# Tweeter_Right.net
KiCad netlist of a schematic drawn in Altium Designer
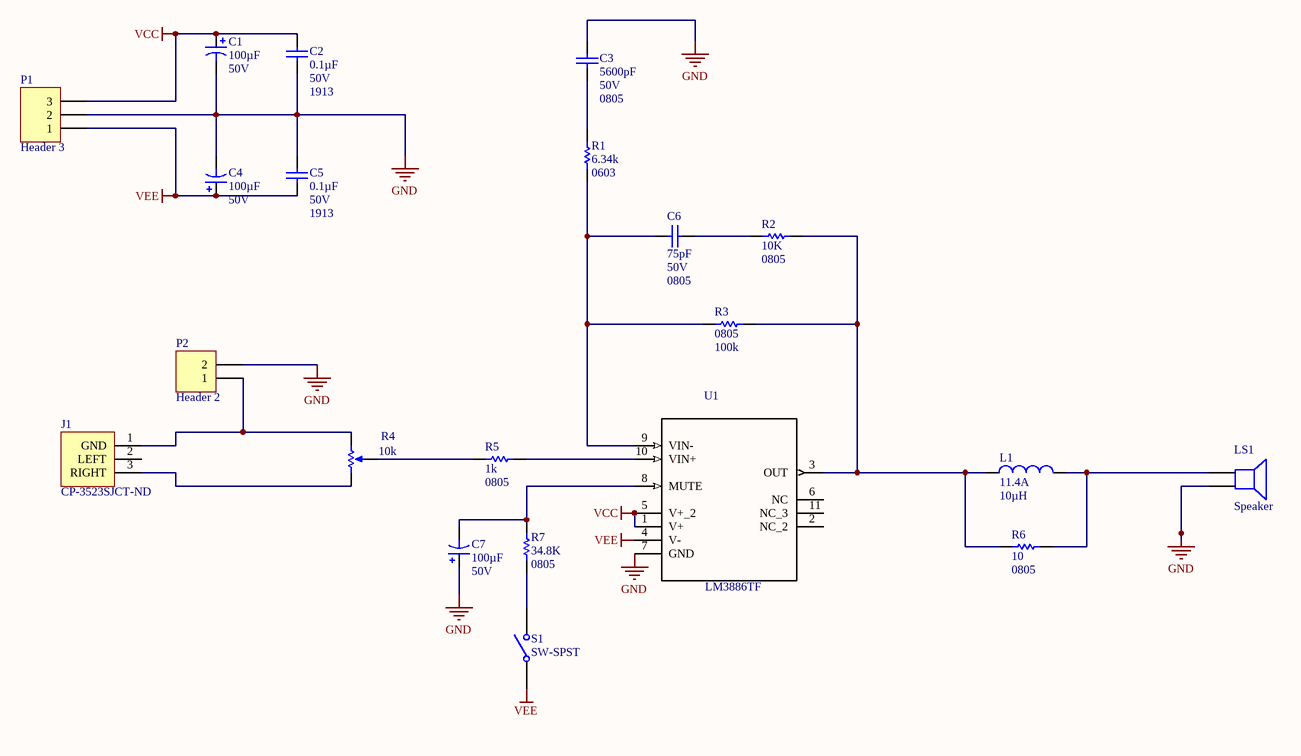
[diagram p0: Tweeter Right.SchDoc]

(export (version "E")
  (design (tool "Eeschema 10.0.6"))
  (components
    (comp (ref "C1")
      (value "UUQ1H101MCL1GS")
      (footprint "CAPAE109103X103M")
      (description "CAP ALUM 100UF 20% 50V SMD")
      (fields
        (field (name "TOLERANCE") "±20%")
        (field (name "CAPACITANCE") "100µF")
        (field (name "VOLTAGE - RATED") "50V")
      )
      (libsource (lib "Capacitors") (part "UUQ1H101MCL1GS"))
    )
    (comp (ref "C2")
      (value "ECH-U1H104JX9")
      (footprint "CAP1913")
      (description "CAP FILM 0.1UF 5% 50VDC 1913")
      (fields
        (field (name "TOLERANCE") "±5%")
        (field (name "CAPACITANCE") "0.1µF")
        (field (name "VOLTAGE RATING - DC") "50V")
        (field (name "PACKAGE / CASE") "1913")
      )
      (libsource (lib "Capacitors") (part "ECH-U1H104JX9"))
    )
    (comp (ref "C3")
      (value "C2012C0G1H562J060AA")
      (footprint "CAP0805")
      (description "CAP CER 5600PF 50V C0G 0805")
      (fields
        (field (name "CAPACITANCE") "5600pF")
        (field (name "VOLTAGE - RATED") "50V")
        (field (name "PACKAGE") "0805")
      )
      (libsource (lib "Capacitors") (part "C2012C0G1H562J060AA"))
    )
    (comp (ref "C4")
      (value "UUQ1H101MCL1GS")
      (footprint "CAPAE109103X103M")
      (description "CAP ALUM 100UF 20% 50V SMD")
      (fields
        (field (name "TOLERANCE") "±20%")
        (field (name "CAPACITANCE") "100µF")
        (field (name "VOLTAGE - RATED") "50V")
      )
      (libsource (lib "Capacitors") (part "UUQ1H101MCL1GS"))
    )
    (comp (ref "C5")
      (value "ECH-U1H104JX9")
      (footprint "CAP1913")
      (description "CAP FILM 0.1UF 5% 50VDC 1913")
      (fields
        (field (name "TOLERANCE") "±5%")
        (field (name "CAPACITANCE") "0.1µF")
        (field (name "VOLTAGE RATING - DC") "50V")
        (field (name "PACKAGE / CASE") "1913")
      )
      (libsource (lib "Capacitors") (part "ECH-U1H104JX9"))
    )
    (comp (ref "C6")
      (value "C0805C750J5GAC7800")
      (footprint "CAP0805")
      (description "CAP CER 75PF 50V NP0 0805")
      (fields
        (field (name "CAPACITANCE") "75pF")
        (field (name "VOLTAGE - RATED") "50V")
        (field (name "PACKAGE") "0805")
      )
      (libsource (lib "Capacitors") (part "C0805C750J5GAC7800"))
    )
    (comp (ref "C7")
      (value "UUQ1H101MCL1GS")
      (footprint "CAPAE109103X103M")
      (description "CAP ALUM 100UF 20% 50V SMD")
      (fields
        (field (name "TOLERANCE") "±20%")
        (field (name "CAPACITANCE") "100µF")
        (field (name "VOLTAGE - RATED") "50V")
      )
      (libsource (lib "Capacitors") (part "UUQ1H101MCL1GS"))
    )
    (comp (ref "J1")
      (value "SJ-3523-SMT-TR")
      (footprint "CONN JACK STEREO 3.5MM SMD R/A")
      (description "CONN JACK STEREO 3.5MM SMD R/A")
      (fields (field (name "SUPPLIER PART NUMBER 1") "CP-3523SJCT-ND"))
      (libsource (lib "Mechanical_Devices") (part "SJ-3523-SMT-TR"))
    )
    (comp (ref "L1")
      (value "2100LL-100-V-RC")
      (footprint "Shielded Toroidal Inductor")
      (description "FIXED IND 10UH 11.4A 5 MOHM TH")
      (fields
        (field (name "TOLERANCE") "±15%")
        (field (name "CURRENT RATING") "11.4A")
        (field (name "INDUCTANCE") "10µH")
      )
      (libsource (lib "Inductors") (part "2100LL-100-V-RC"))
    )
    (comp (ref "LS1")
      (value "Speaker")
      (footprint "PIN2")
      (description "Loudspeaker")
      (fields (field (name "PUBLISHER") "Altium Limited"))
      (libsource (lib "Miscellaneous Devices") (part "Speaker"))
    )
    (comp (ref "P1")
      (value "Header 3")
      (footprint "HDR1X3")
      (description "Header, 3-Pin")
      (fields (field (name "PUBLISHER") "Altium Limited"))
      (libsource (lib "Miscellaneous Connectors") (part "Header 3"))
    )
    (comp (ref "P2")
      (value "Header 2")
      (footprint "HDR1X2")
      (description "Header, 2-Pin")
      (fields (field (name "PUBLISHER") "Altium Limited"))
      (libsource (lib "Miscellaneous Connectors") (part "Header 2"))
    )
    (comp (ref "R1")
      (value "RT0603DRD076K34L")
      (footprint "RES0603")
      (description "RES SMD 6.34KOHM 0.5% 1/10W 0603")
      (fields (field (name "RESISTANCE") "6.34k") (field (name "PACKAGE") "0603"))
      (libsource (lib "Resistors") (part "RT0603DRD076K34L"))
    )
    (comp (ref "R2")
      (value "RT0805BRE0710KL")
      (footprint "RES0805")
      (description "RES SMD 10K OHM 0.1% 1/8W 0805")
      (fields (field (name "RESISTANCE") "10K") (field (name "PACKAGE") "0805"))
      (libsource (lib "Resistors") (part "RT0805BRE0710KL"))
    )
    (comp (ref "R3")
      (value "ERA-6AEB104V")
      (footprint "RES0805")
      (description "RES SMD 100K OHM 0.1% 1/8W 0805")
      (fields (field (name "PACKAGE") "0805") (field (name "RESISTANCE") "100k"))
      (libsource (lib "Resistors") (part "ERA-6AEB104V"))
    )
    (comp (ref "R4")
      (value "10k")
      (footprint "VR5")
      (description "Potentiometer")
      (fields (field (name "Comment") "RPot") (field (name "PUBLISHER") "Altium Limited"))
      (libsource (lib "Miscellaneous Devices") (part "RPot"))
    )
    (comp (ref "R5")
      (value "RT0805FRE071KL")
      (footprint "RES0805")
      (description "RES SMD 1K OHM 1% 1/8W 0805")
      (fields (field (name "RESISTANCE") "1k") (field (name "PACKAGE") "0805"))
      (libsource (lib "Resistors") (part "RT0805FRE071KL"))
    )
    (comp (ref "R6")
      (value "RNCP0805FTD10R0")
      (footprint "RES0805")
      (description "RES 10 OHM 1% 1/4W 0805")
      (fields
        (field (name "TOLERANCE") "±1%")
        (field (name "RESISTANCE") "10")
        (field (name "PACKAGE") "0805")
      )
      (libsource (lib "Resistors") (part "RNCP0805FTD10R0"))
    )
    (comp (ref "R7")
      (value "RT0805DRD0734K8L")
      (footprint "RES0805")
      (description "RES SMD 34.8K OHM 0.5% 1/8W 0805")
      (fields (field (name "RESISTANCE") "34.8K") (field (name "PACKAGE") "0805"))
      (libsource (lib "Resistors") (part "RT0805DRD0734K8L"))
    )
    (comp (ref "S1")
      (value "SW-SPST")
      (footprint "SPST-2")
      (description "Single-Pole, Single-Throw Switch")
      (fields (field (name "PUBLISHER") "Altium Limited"))
      (libsource (lib "Miscellaneous Devices") (part "SW-SPST"))
    )
    (comp (ref "U1")
      (value "LM3886TF")
      (footprint "AMP_LM3886T")
      (fields (field (name "MF") "Texas"))
      (libsource (lib "LM3886TF") (part "LM3886TF"))
    )
  )
  (nets
    (net (code "1") (name "GND") (class "Default")
      (node (ref "C1") (pin "2") (pinfunction "2_2") (pintype "passive"))
      (node (ref "C2") (pin "1") (pinfunction "1_1") (pintype "passive"))
      (node (ref "C3") (pin "2") (pinfunction "2_2") (pintype "passive"))
      (node (ref "C4") (pin "2") (pinfunction "2_2") (pintype "passive"))
      (node (ref "C5") (pin "2") (pinfunction "2_2") (pintype "passive"))
      (node (ref "C7") (pin "1") (pinfunction "1_1") (pintype "passive"))
      (node (ref "LS1") (pin "2") (pinfunction "2_2") (pintype "passive"))
      (node (ref "P1") (pin "2") (pinfunction "2_2") (pintype "passive"))
      (node (ref "P2") (pin "2") (pinfunction "2_2") (pintype "passive"))
      (node (ref "U1") (pin "7") (pinfunction "GND_7") (pintype "power_in"))
    )
    (net (code "2") (name "Net-(C3-Pad1)") (class "Default")
      (node (ref "C3") (pin "1") (pinfunction "1_1") (pintype "passive"))
      (node (ref "R1") (pin "2") (pinfunction "2_2") (pintype "passive"))
    )
    (net (code "3") (name "Net-(C6-Pad2)") (class "Default")
      (node (ref "C6") (pin "2") (pinfunction "2_2") (pintype "passive"))
      (node (ref "R2") (pin "1") (pinfunction "1_1") (pintype "passive"))
    )
    (net (code "4") (name "Net-(J1-GND)") (class "Default")
      (node (ref "J1") (pin "1") (pinfunction "GND_1") (pintype "passive"))
      (node (ref "P2") (pin "1") (pinfunction "1_1") (pintype "passive"))
      (node (ref "R4") (pin "2") (pinfunction "BOT_2") (pintype "passive"))
    )
    (net (code "5") (name "Net-(J1-RIGHT)") (class "Default")
      (node (ref "J1") (pin "3") (pinfunction "RIGHT_3") (pintype "passive"))
      (node (ref "R4") (pin "1") (pinfunction "TOP_1") (pintype "passive"))
    )
    (net (code "6") (name "Net-(L1-Pad2)") (class "Default")
      (node (ref "L1") (pin "2") (pinfunction "2_2") (pintype "passive"))
      (node (ref "LS1") (pin "1") (pinfunction "1_1") (pintype "passive"))
      (node (ref "R6") (pin "2") (pinfunction "2_2") (pintype "passive"))
    )
    (net (code "7") (name "Net-(R4-TAP)") (class "Default")
      (node (ref "R4") (pin "3") (pinfunction "TAP_3") (pintype "passive"))
      (node (ref "R5") (pin "1") (pinfunction "1_1") (pintype "passive"))
    )
    (net (code "8") (name "Net-(S1-NO)") (class "Default")
      (node (ref "R7") (pin "1") (pinfunction "1_1") (pintype "passive"))
      (node (ref "S1") (pin "2") (pinfunction "NO_2") (pintype "passive"))
    )
    (net (code "9") (name "Net-(U1-MUTE)") (class "Default")
      (node (ref "C7") (pin "2") (pinfunction "2_2") (pintype "passive"))
      (node (ref "R7") (pin "2") (pinfunction "2_2") (pintype "passive"))
      (node (ref "U1") (pin "8") (pinfunction "MUTE_8") (pintype "input"))
    )
    (net (code "10") (name "Net-(U1-OUT)") (class "Default")
      (node (ref "L1") (pin "1") (pinfunction "1_1") (pintype "passive"))
      (node (ref "R2") (pin "2") (pinfunction "2_2") (pintype "passive"))
      (node (ref "R3") (pin "2") (pinfunction "2_2") (pintype "passive"))
      (node (ref "R6") (pin "1") (pinfunction "1_1") (pintype "passive"))
      (node (ref "U1") (pin "3") (pinfunction "OUT_3") (pintype "output"))
    )
    (net (code "11") (name "Net-(U1-VIN+)") (class "Default")
      (node (ref "R5") (pin "2") (pinfunction "2_2") (pintype "passive"))
      (node (ref "U1") (pin "10") (pinfunction "VIN+_10") (pintype "input"))
    )
    (net (code "12") (name "Net-(U1-VIN-)") (class "Default")
      (node (ref "C6") (pin "1") (pinfunction "1_1") (pintype "passive"))
      (node (ref "R1") (pin "1") (pinfunction "1_1") (pintype "passive"))
      (node (ref "R3") (pin "1") (pinfunction "1_1") (pintype "passive"))
      (node (ref "U1") (pin "9") (pinfunction "VIN-_9") (pintype "input"))
    )
    (net (code "13") (name "VCC") (class "Default")
      (node (ref "C1") (pin "1") (pinfunction "1_1") (pintype "passive"))
      (node (ref "C2") (pin "2") (pinfunction "2_2") (pintype "passive"))
      (node (ref "P1") (pin "3") (pinfunction "3_3") (pintype "passive"))
      (node (ref "U1") (pin "1") (pinfunction "V+_1") (pintype "power_in"))
      (node (ref "U1") (pin "5") (pinfunction "V+_2_5") (pintype "power_in"))
    )
    (net (code "14") (name "VEE") (class "Default")
      (node (ref "C4") (pin "1") (pinfunction "1_1") (pintype "passive"))
      (node (ref "C5") (pin "1") (pinfunction "1_1") (pintype "passive"))
      (node (ref "P1") (pin "1") (pinfunction "1_1") (pintype "passive"))
      (node (ref "S1") (pin "1") (pinfunction "COMMON_1") (pintype "passive"))
      (node (ref "U1") (pin "4") (pinfunction "V-_4") (pintype "power_in"))
    )
    (net (code "15") (name "unconnected-(J1-LEFT-Pad2)") (class "Default")
      (node (ref "J1") (pin "2") (pinfunction "LEFT_2") (pintype "passive"))
    )
    (net (code "16") (name "unconnected-(U1-NC-Pad6)") (class "Default")
      (node (ref "U1") (pin "6") (pinfunction "NC_6") (pintype "passive"))
    )
    (net (code "17") (name "unconnected-(U1-NC_2-Pad2)") (class "Default")
      (node (ref "U1") (pin "2") (pinfunction "NC_2_2") (pintype "passive"))
    )
    (net (code "18") (name "unconnected-(U1-NC_3-Pad11)") (class "Default")
      (node (ref "U1") (pin "11") (pinfunction "NC_3_11") (pintype "passive"))
    )
  )
)
